# BOOSTController2.net
KiCad netlist of a schematic drawn in Altium Designer
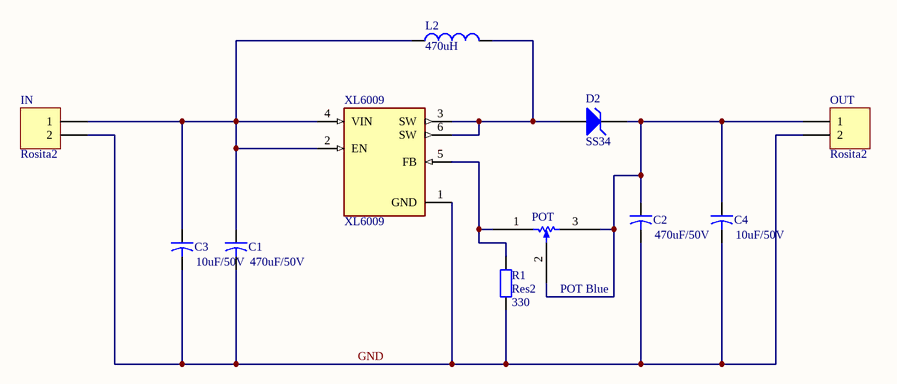
[diagram p0: BOOSTController2.SchDoc]

(export (version "E")
  (design (tool "Eeschema 10.0.6"))
  (components
    (comp (ref "C1")
      (value "470uF/50V")
      (footprint "SMC7343P")
      (description "Capacitor")
      (fields (field (name "PUBLISHER") "Altium Limited"))
      (libsource (lib "Miscellaneous Devices") (part "Cap2"))
    )
    (comp (ref "C2")
      (value "470uF/50V")
      (footprint "SMC7343P")
      (description "Capacitor")
      (fields (field (name "PUBLISHER") "Altium Limited"))
      (libsource (lib "Miscellaneous Devices") (part "Cap2"))
    )
    (comp (ref "C3")
      (value "10uF/50V")
      (footprint "SMC7343P")
      (description "Capacitor")
      (fields (field (name "PUBLISHER") "Altium Limited"))
      (libsource (lib "Miscellaneous Devices") (part "Cap2"))
    )
    (comp (ref "C4")
      (value "10uF/50V")
      (footprint "SMC7343P")
      (description "Capacitor")
      (fields (field (name "PUBLISHER") "Altium Limited"))
      (libsource (lib "Miscellaneous Devices") (part "Cap2"))
    )
    (comp (ref "D2")
      (value "SS34")
      (footprint "SMC")
      (description "Schottky Diode [SS34]")
      (fields (field (name "PUBLISHER") "Altium Limited"))
      (libsource (lib "Miscellaneous Devices") (part "D Zener"))
    )
    (comp (ref "IN") (value "Rosita2") (footprint "Rosita2") (libsource (lib "TriacBoard") (part "Rosita2")))
    (comp (ref "L2")
      (value "470uH")
      (footprint "L125")
      (description "Inductor")
      (fields (field (name "PUBLISHER") "Altium Limited"))
      (libsource (lib "Miscellaneous Devices") (part "Inductor"))
    )
    (comp (ref "OUT") (value "Rosita2") (footprint "Rosita2") (libsource (lib "") (part "Rosita2_1")))
    (comp (ref "POT")
      (value "POT Blue")
      (footprint "POT - Blue")
      (libsource (lib "TriacBoard") (part "POT Blue"))
    )
    (comp (ref "R1")
      (value "Res2")
      (footprint "AXIAL-0.4")
      (description "Resistor")
      (fields (field (name "ALTIUM_VALUE") "330") (field (name "PUBLISHER") "Altium Limited"))
      (libsource (lib "Miscellaneous Devices") (part "Res2"))
    )
    (comp (ref "XL6009") (value "XL6009") (footprint "XL6009") (libsource (lib "TriacBoard") (part "XL6009")))
  )
  (nets
    (net (code "1") (name "/GND") (class "Default")
      (node (ref "C1") (pin "2") (pinfunction "2_2") (pintype "passive"))
      (node (ref "C2") (pin "2") (pinfunction "2_2") (pintype "passive"))
      (node (ref "C3") (pin "2") (pinfunction "2_2") (pintype "passive"))
      (node (ref "C4") (pin "2") (pinfunction "2_2") (pintype "passive"))
      (node (ref "IN") (pin "2") (pinfunction "2_2") (pintype "passive"))
      (node (ref "OUT") (pin "2") (pinfunction "2_2") (pintype "passive"))
      (node (ref "R1") (pin "1") (pinfunction "1_1") (pintype "passive"))
      (node (ref "XL6009") (pin "1") (pinfunction "GND_1") (pintype "power_in"))
    )
    (net (code "2") (name "Net-(D2-A)") (class "Default")
      (node (ref "D2") (pin "1") (pinfunction "A_1") (pintype "passive"))
      (node (ref "L2") (pin "2") (pinfunction "2_2") (pintype "passive"))
      (node (ref "XL6009") (pin "3") (pinfunction "SW_3") (pintype "output"))
      (node (ref "XL6009") (pin "6") (pinfunction "SW_6") (pintype "output"))
    )
    (net (code "3") (name "Net-(D2-K)") (class "Default")
      (node (ref "C2") (pin "1") (pinfunction "1_1") (pintype "passive"))
      (node (ref "C4") (pin "1") (pinfunction "1_1") (pintype "passive"))
      (node (ref "D2") (pin "2") (pinfunction "K_2") (pintype "passive"))
      (node (ref "OUT") (pin "1") (pinfunction "1_1") (pintype "passive"))
      (node (ref "POT") (pin "2") (pintype "passive"))
      (node (ref "POT") (pin "3") (pintype "passive"))
    )
    (net (code "4") (name "Net-(XL6009-EN)") (class "Default")
      (node (ref "C1") (pin "1") (pinfunction "1_1") (pintype "passive"))
      (node (ref "C3") (pin "1") (pinfunction "1_1") (pintype "passive"))
      (node (ref "IN") (pin "1") (pinfunction "1_1") (pintype "passive"))
      (node (ref "L2") (pin "1") (pinfunction "1_1") (pintype "passive"))
      (node (ref "XL6009") (pin "2") (pinfunction "EN_2") (pintype "input"))
      (node (ref "XL6009") (pin "4") (pinfunction "VIN_4") (pintype "input"))
    )
    (net (code "5") (name "Net-(XL6009-FB)") (class "Default")
      (node (ref "POT") (pin "1") (pintype "passive"))
      (node (ref "R1") (pin "2") (pinfunction "2_2") (pintype "passive"))
      (node (ref "XL6009") (pin "5") (pinfunction "FB_5") (pintype "input"))
    )
  )
)
